# battery.net
KiCad netlist of a schematic drawn in EAGLE
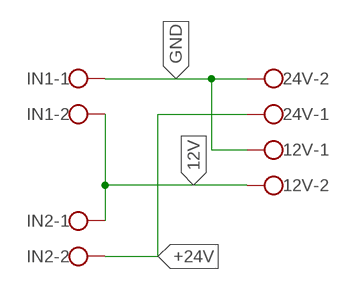
[diagram p0: schematic, sheet 1]

(export (version "E")
  (design (tool "Eeschema 10.0.6"))
  (components
    (comp (ref "12V")
      (value "W237-113")
      (footprint "eagle-import:W237-113")
      (libsource (lib "eagle-import") (part "W237-113"))
    )
    (comp (ref "24V")
      (value "W237-113")
      (footprint "eagle-import:W237-113")
      (libsource (lib "eagle-import") (part "W237-113"))
    )
    (comp (ref "IN1")
      (value "W237-113")
      (footprint "eagle-import:W237-113")
      (libsource (lib "eagle-import") (part "W237-113"))
    )
    (comp (ref "IN2")
      (value "W237-113")
      (footprint "eagle-import:W237-113")
      (libsource (lib "eagle-import") (part "W237-113"))
    )
  )
  (nets
    (net (code "1") (name "+24V") (class "Default")
      (node (ref "24V") (pin "1") (pinfunction "KL_1") (pintype "passive"))
      (node (ref "IN2") (pin "2") (pinfunction "KL_2") (pintype "passive"))
    )
    (net (code "2") (name "12V") (class "Default")
      (node (ref "12V") (pin "2") (pinfunction "KL_2") (pintype "passive"))
      (node (ref "IN1") (pin "2") (pinfunction "KL_2") (pintype "passive"))
      (node (ref "IN2") (pin "1") (pinfunction "KL_1") (pintype "passive"))
    )
    (net (code "3") (name "GND") (class "Default")
      (node (ref "12V") (pin "1") (pinfunction "KL_1") (pintype "passive"))
      (node (ref "24V") (pin "2") (pinfunction "KL_2") (pintype "passive"))
      (node (ref "IN1") (pin "1") (pinfunction "KL_1") (pintype "passive"))
    )
  )
)
